# owl-analog.net
KiCad netlist of a schematic drawn in EAGLE
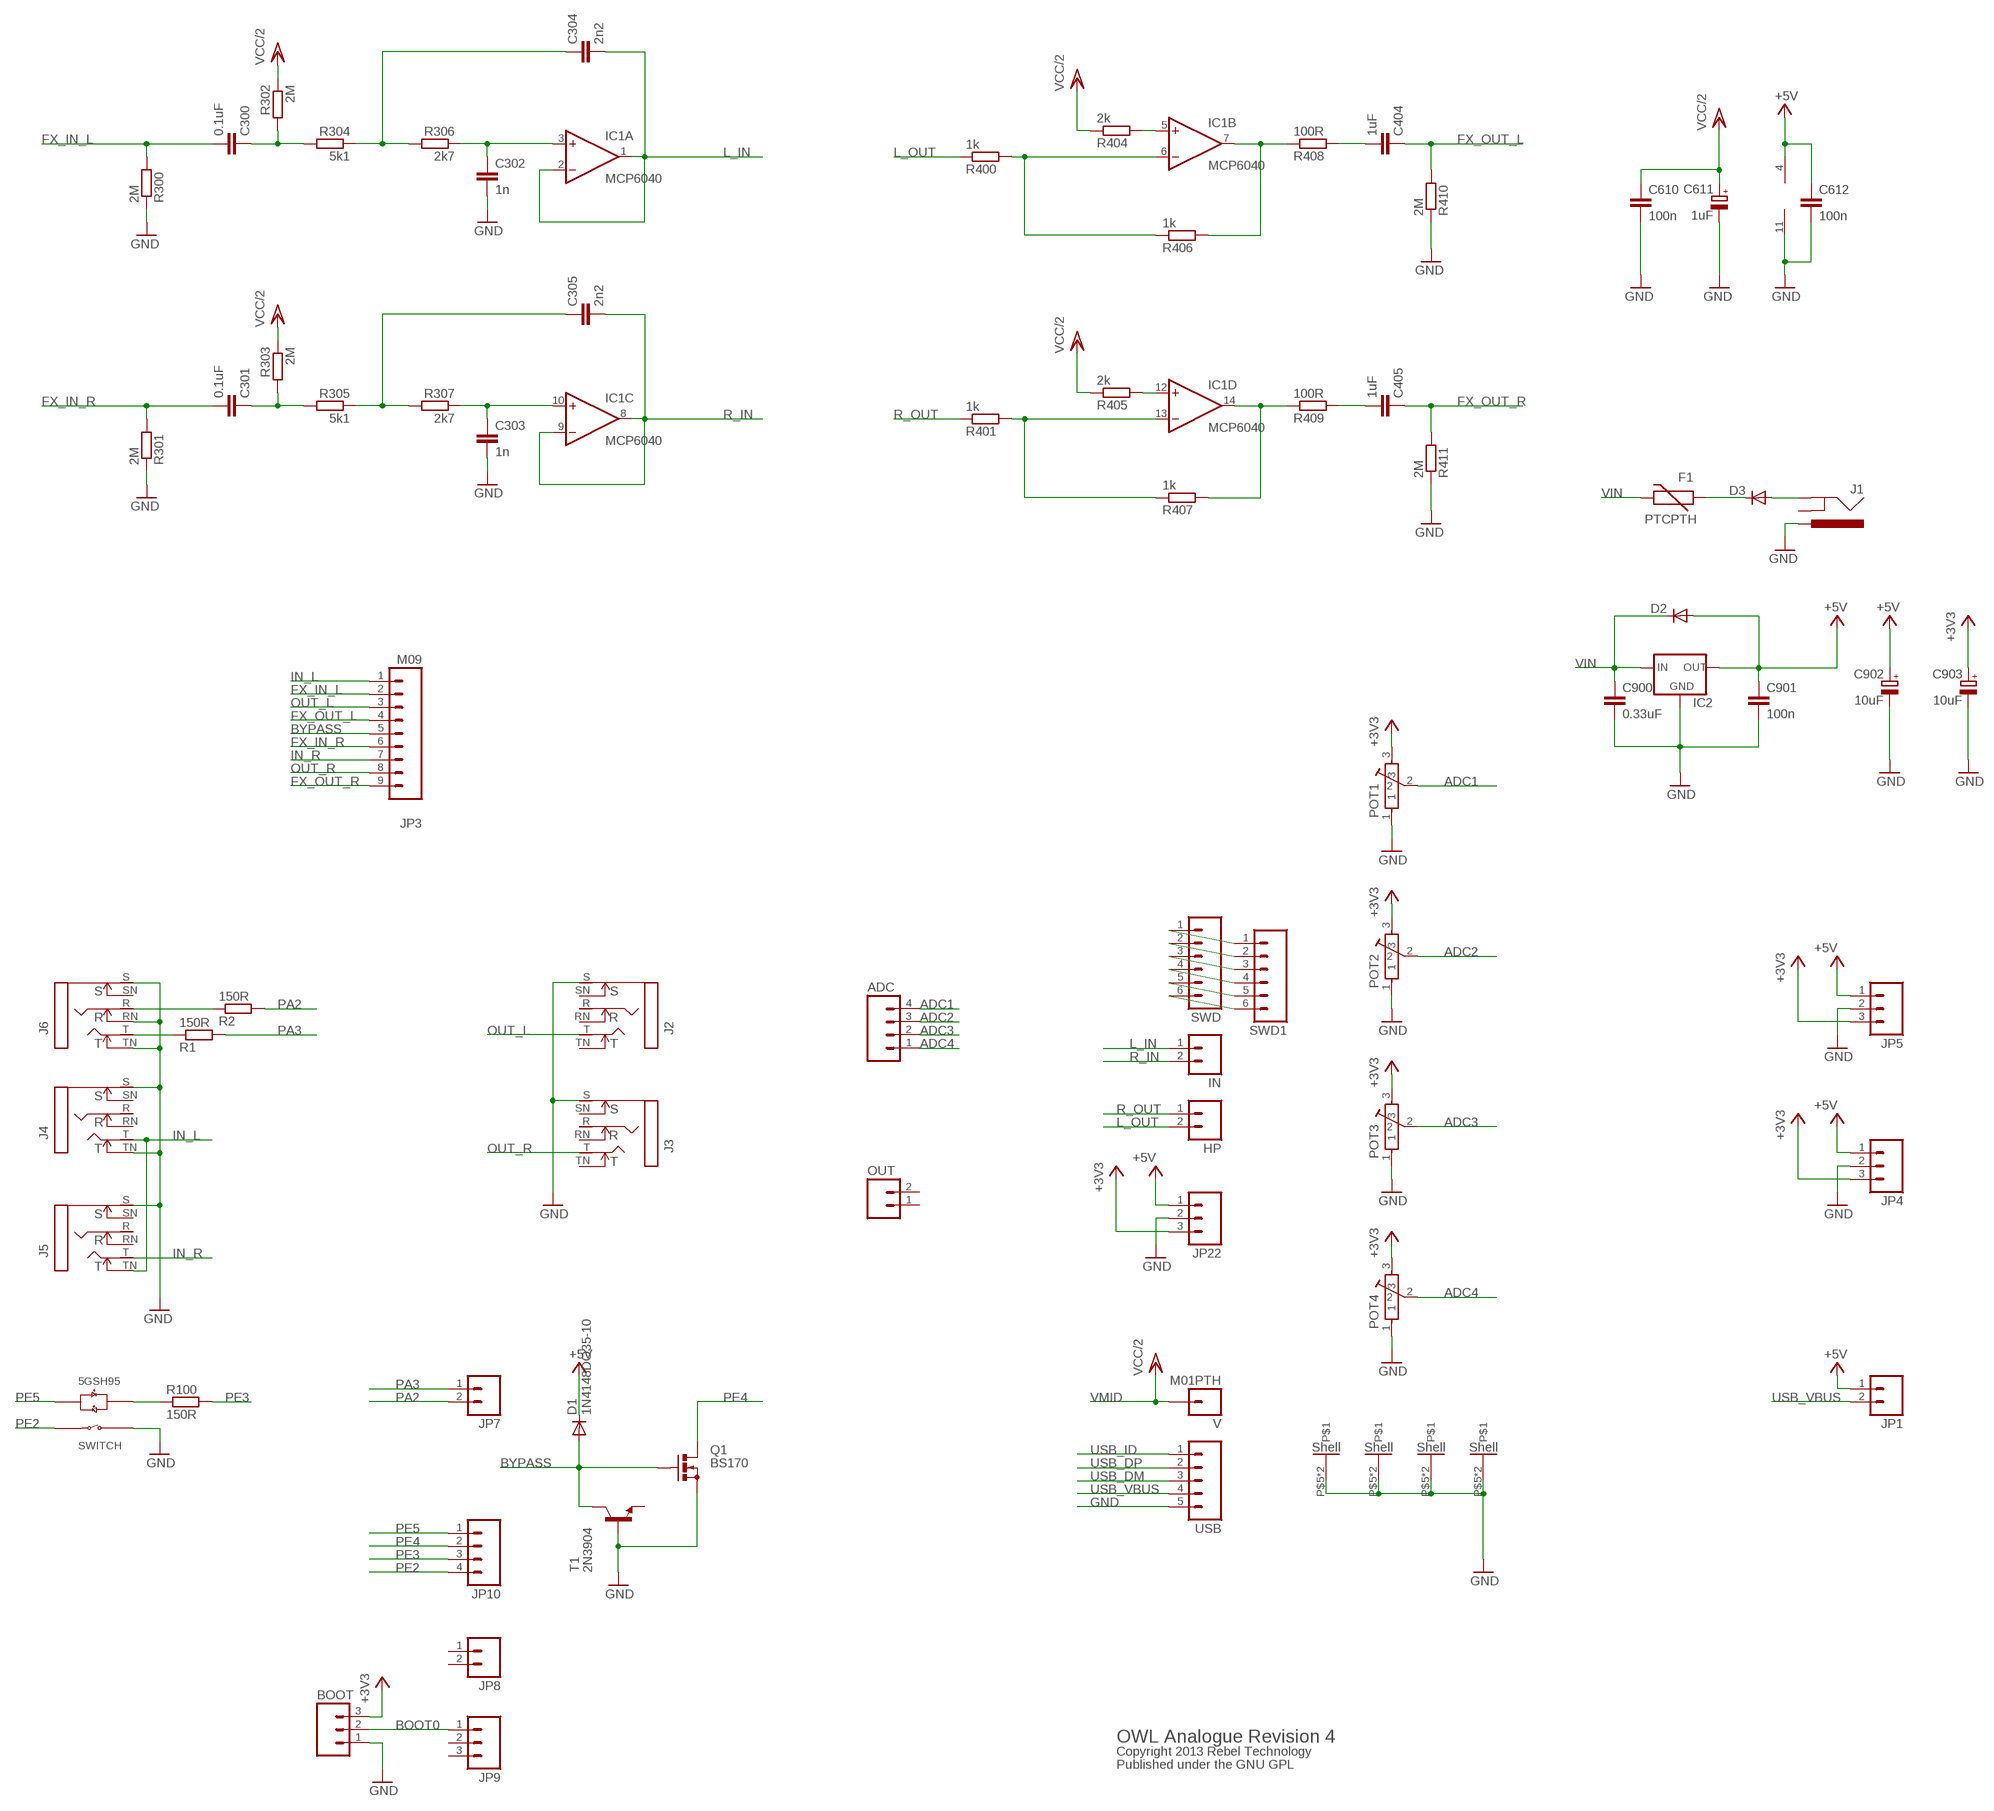
[diagram p0: schematic, sheet 1]

(export (version "E")
  (design (tool "Eeschema 10.0.6"))
  (components
    (comp (ref "ADC")
      (value "M04PTH")
      (footprint "eagle-import:1X04")
      (libsource (lib "eagle-import") (part "M04PTH"))
    )
    (comp (ref "BOOT")
      (value "M03PTH")
      (footprint "eagle-import:1X03")
      (libsource (lib "eagle-import") (part "M03PTH"))
    )
    (comp (ref "C300")
      (value "0.1uF")
      (footprint "eagle-import:C5B3.5")
      (libsource (lib "eagle-import") (part "C5/3.5"))
    )
    (comp (ref "C301")
      (value "0.1uF")
      (footprint "eagle-import:C5B3.5")
      (libsource (lib "eagle-import") (part "C5/3.5"))
    )
    (comp (ref "C302")
      (value "1n")
      (footprint "eagle-import:C5B2.5")
      (libsource (lib "eagle-import") (part "C5/2.5"))
    )
    (comp (ref "C303")
      (value "1n")
      (footprint "eagle-import:C5B2.5")
      (libsource (lib "eagle-import") (part "C5/2.5"))
    )
    (comp (ref "C304")
      (value "2n2")
      (footprint "eagle-import:C5B2.5")
      (libsource (lib "eagle-import") (part "C5/2.5"))
    )
    (comp (ref "C305")
      (value "2n2")
      (footprint "eagle-import:C050-025X075")
      (libsource (lib "eagle-import") (part "C-EU050-025X075"))
    )
    (comp (ref "C404")
      (value "1uF")
      (footprint "eagle-import:C5B5")
      (libsource (lib "eagle-import") (part "C5/5"))
    )
    (comp (ref "C405")
      (value "1uF")
      (footprint "eagle-import:C5B5")
      (libsource (lib "eagle-import") (part "C5/5"))
    )
    (comp (ref "C610")
      (value "100n")
      (footprint "eagle-import:C050-025X075")
      (libsource (lib "eagle-import") (part "C-EU050-025X075"))
    )
    (comp (ref "C611")
      (value "1uF")
      (footprint "eagle-import:E2,5-7")
      (libsource (lib "eagle-import") (part "CPOL-EUE2.5-7"))
    )
    (comp (ref "C612")
      (value "100n")
      (footprint "eagle-import:C050-025X075")
      (libsource (lib "eagle-import") (part "C-EU050-025X075"))
    )
    (comp (ref "C900")
      (value "0.33uF")
      (footprint "eagle-import:C050-025X075")
      (libsource (lib "eagle-import") (part "C-EU050-025X075"))
    )
    (comp (ref "C901")
      (value "100n")
      (footprint "eagle-import:C050-025X075")
      (libsource (lib "eagle-import") (part "C-EU050-025X075"))
    )
    (comp (ref "C902")
      (value "10uF")
      (footprint "eagle-import:E2,5-7")
      (libsource (lib "eagle-import") (part "CPOL-EUE2.5-7"))
    )
    (comp (ref "C903")
      (value "10uF")
      (footprint "eagle-import:E2,5-7")
      (libsource (lib "eagle-import") (part "CPOL-EUE2.5-7"))
    )
    (comp (ref "D1")
      (value "1N4148DO35-10")
      (footprint "eagle-import:DO35-10")
      (libsource (lib "eagle-import") (part "1N4148DO35-10"))
    )
    (comp (ref "D2")
      (value "DIODE1N4001")
      (footprint "eagle-import:DIODE-1N4001")
      (libsource (lib "eagle-import") (part "DIODE1N4001"))
    )
    (comp (ref "D3")
      (value "DIODE1N4001")
      (footprint "eagle-import:DIODE-1N4001")
      (libsource (lib "eagle-import") (part "DIODE1N4001"))
    )
    (comp (ref "F1")
      (value "PTCPTH")
      (footprint "eagle-import:PTC")
      (libsource (lib "eagle-import") (part "PTCPTH"))
    )
    (comp (ref "HP")
      (value "M02PTH")
      (footprint "eagle-import:1X02")
      (libsource (lib "eagle-import") (part "M02PTH"))
    )
    (comp (ref "IC1")
      (value "MCP6040")
      (footprint "eagle-import:DIL14")
      (libsource (lib "eagle-import") (part "TL074P"))
    )
    (comp (ref "IC2")
      (value "V_REG_78XX-TO-220")
      (footprint "eagle-import:TO-220-ALT")
      (libsource (lib "eagle-import") (part "V_REG_78XX-TO-220"))
    )
    (comp (ref "IN")
      (value "M02PTH")
      (footprint "eagle-import:1X02")
      (libsource (lib "eagle-import") (part "M02PTH"))
    )
    (comp (ref "J1")
      (value "POWER_JACKPTH")
      (footprint "eagle-import:POWER_JACK_PTH")
      (libsource (lib "eagle-import") (part "POWER_JACKPTH"))
    )
    (comp (ref "J2")
      (value "NEUTRIK_NMJ6HCD2")
      (footprint "eagle-import:NMJ6HCD2")
      (libsource (lib "eagle-import") (part "NEUTRIK_NMJ6HCD2"))
    )
    (comp (ref "J3")
      (value "NEUTRIK_NMJ6HCD2")
      (footprint "eagle-import:NMJ6HCD2")
      (libsource (lib "eagle-import") (part "NEUTRIK_NMJ6HCD2"))
    )
    (comp (ref "J4")
      (value "NEUTRIK_NMJ6HCD2")
      (footprint "eagle-import:NMJ6HCD2")
      (libsource (lib "eagle-import") (part "NEUTRIK_NMJ6HCD2"))
    )
    (comp (ref "J5")
      (value "NEUTRIK_NMJ6HCD2")
      (footprint "eagle-import:NMJ6HCD2")
      (libsource (lib "eagle-import") (part "NEUTRIK_NMJ6HCD2"))
    )
    (comp (ref "J6")
      (value "NEUTRIK_NMJ6HCD2")
      (footprint "eagle-import:NMJ6HCD2")
      (libsource (lib "eagle-import") (part "NEUTRIK_NMJ6HCD2"))
    )
    (comp (ref "JP1")
      (value "M02PTH")
      (footprint "eagle-import:1X02")
      (libsource (lib "eagle-import") (part "M02PTH"))
    )
    (comp (ref "JP3")
      (value "M09")
      (footprint "eagle-import:1X09")
      (libsource (lib "eagle-import") (part "M09"))
    )
    (comp (ref "JP4")
      (value "M03PTH")
      (footprint "eagle-import:1X03")
      (libsource (lib "eagle-import") (part "M03PTH"))
    )
    (comp (ref "JP5")
      (value "M03PTH")
      (footprint "eagle-import:1X03")
      (libsource (lib "eagle-import") (part "M03PTH"))
    )
    (comp (ref "JP7")
      (value "M02PTH")
      (footprint "eagle-import:1X02")
      (libsource (lib "eagle-import") (part "M02PTH"))
    )
    (comp (ref "JP8")
      (value "M02PTH")
      (footprint "eagle-import:1X02")
      (libsource (lib "eagle-import") (part "M02PTH"))
    )
    (comp (ref "JP9")
      (value "M03PTH")
      (footprint "eagle-import:1X03")
      (libsource (lib "eagle-import") (part "M03PTH"))
    )
    (comp (ref "JP10")
      (value "M04PTH")
      (footprint "eagle-import:1X04")
      (libsource (lib "eagle-import") (part "M04PTH"))
    )
    (comp (ref "JP22")
      (value "M03PTH")
      (footprint "eagle-import:1X03")
      (libsource (lib "eagle-import") (part "M03PTH"))
    )
    (comp (ref "OUT")
      (value "M02PTH")
      (footprint "eagle-import:1X02")
      (libsource (lib "eagle-import") (part "M02PTH"))
    )
    (comp (ref "POT1")
      (value "POT-ALPS-RK09L1140")
      (footprint "eagle-import:POT-ALPS-RK09L1140")
      (libsource (lib "eagle-import") (part "POT-ALPS-RK09L1140"))
    )
    (comp (ref "POT2")
      (value "POT-ALPS-RK09L1140")
      (footprint "eagle-import:POT-ALPS-RK09L1140")
      (libsource (lib "eagle-import") (part "POT-ALPS-RK09L1140"))
    )
    (comp (ref "POT3")
      (value "POT-ALPS-RK09L1140")
      (footprint "eagle-import:POT-ALPS-RK09L1140")
      (libsource (lib "eagle-import") (part "POT-ALPS-RK09L1140"))
    )
    (comp (ref "POT4")
      (value "POT-ALPS-RK09L1140")
      (footprint "eagle-import:POT-ALPS-RK09L1140")
      (libsource (lib "eagle-import") (part "POT-ALPS-RK09L1140"))
    )
    (comp (ref "Q1")
      (value "BS170")
      (footprint "eagle-import:SOT54E")
      (libsource (lib "eagle-import") (part "BS170"))
    )
    (comp (ref "R1")
      (value "150R")
      (footprint "eagle-import:0204_7")
      (libsource (lib "eagle-import") (part "R-EU_0204/7"))
    )
    (comp (ref "R2")
      (value "150R")
      (footprint "eagle-import:0204_7")
      (libsource (lib "eagle-import") (part "R-EU_0204/7"))
    )
    (comp (ref "R100")
      (value "150R")
      (footprint "eagle-import:0204_7")
      (libsource (lib "eagle-import") (part "R-EU_0204/7"))
    )
    (comp (ref "R300")
      (value "2M")
      (footprint "eagle-import:0204_7")
      (libsource (lib "eagle-import") (part "R-EU_0204/7"))
    )
    (comp (ref "R301")
      (value "2M")
      (footprint "eagle-import:0204_7")
      (libsource (lib "eagle-import") (part "R-EU_0204/7"))
    )
    (comp (ref "R302")
      (value "2M")
      (footprint "eagle-import:0204_7")
      (libsource (lib "eagle-import") (part "R-EU_0204/7"))
    )
    (comp (ref "R303")
      (value "2M")
      (footprint "eagle-import:0204_7")
      (libsource (lib "eagle-import") (part "R-EU_0204/7"))
    )
    (comp (ref "R304")
      (value "5k1")
      (footprint "eagle-import:0204_7")
      (libsource (lib "eagle-import") (part "R-EU_0204/7"))
    )
    (comp (ref "R305")
      (value "5k1")
      (footprint "eagle-import:0204_7")
      (libsource (lib "eagle-import") (part "R-EU_0204/7"))
    )
    (comp (ref "R306")
      (value "2k7")
      (footprint "eagle-import:0204_7")
      (libsource (lib "eagle-import") (part "R-EU_0204/7"))
    )
    (comp (ref "R307")
      (value "2k7")
      (footprint "eagle-import:0204_7")
      (libsource (lib "eagle-import") (part "R-EU_0204/7"))
    )
    (comp (ref "R400")
      (value "1k")
      (footprint "eagle-import:0204_7")
      (libsource (lib "eagle-import") (part "R-EU_0204/7"))
    )
    (comp (ref "R401")
      (value "1k")
      (footprint "eagle-import:0204_7")
      (libsource (lib "eagle-import") (part "R-EU_0204/7"))
    )
    (comp (ref "R404")
      (value "2k")
      (footprint "eagle-import:0204_7")
      (libsource (lib "eagle-import") (part "R-EU_0204/7"))
    )
    (comp (ref "R405")
      (value "2k")
      (footprint "eagle-import:0204_7")
      (libsource (lib "eagle-import") (part "R-EU_0204/7"))
    )
    (comp (ref "R406")
      (value "1k")
      (footprint "eagle-import:0204_7")
      (libsource (lib "eagle-import") (part "R-EU_0204/7"))
    )
    (comp (ref "R407")
      (value "1k")
      (footprint "eagle-import:0204_7")
      (libsource (lib "eagle-import") (part "R-EU_0204/7"))
    )
    (comp (ref "R408")
      (value "100R")
      (footprint "eagle-import:0204_7")
      (libsource (lib "eagle-import") (part "R-EU_0204/7"))
    )
    (comp (ref "R409")
      (value "100R")
      (footprint "eagle-import:0204_7")
      (libsource (lib "eagle-import") (part "R-EU_0204/7"))
    )
    (comp (ref "R410")
      (value "2M")
      (footprint "eagle-import:0204_7")
      (libsource (lib "eagle-import") (part "R-EU_0204/7"))
    )
    (comp (ref "R411")
      (value "2M")
      (footprint "eagle-import:0204_7")
      (libsource (lib "eagle-import") (part "R-EU_0204/7"))
    )
    (comp (ref "SWD")
      (value "M06SIP")
      (footprint "eagle-import:1X06")
      (libsource (lib "eagle-import") (part "M06SIP"))
    )
    (comp (ref "SWD1")
      (value "M06SIP")
      (footprint "eagle-import:1X06")
      (libsource (lib "eagle-import") (part "M06SIP"))
    )
    (comp (ref "T1")
      (value "2N3904")
      (footprint "eagle-import:TO92")
      (libsource (lib "eagle-import") (part "2N3904"))
    )
    (comp (ref "U$1")
      (value "5GTH9")
      (footprint "eagle-import:5GTH9")
      (libsource (lib "eagle-import") (part "5GTH9"))
    )
    (comp (ref "USB")
      (value "M05PTH")
      (footprint "eagle-import:1X05")
      (libsource (lib "eagle-import") (part "M05PTH"))
    )
    (comp (ref "V")
      (value "M01PTH")
      (footprint "eagle-import:1X01")
      (libsource (lib "eagle-import") (part "M01PTH"))
    )
  )
  (nets
    (net (code "1") (name "+3V3") (class "Default")
      (node (ref "BOOT") (pin "3") (pinfunction "3_3") (pintype "passive"))
      (node (ref "C903") (pin "+") (pinfunction "+_+") (pintype "passive"))
      (node (ref "JP22") (pin "3") (pinfunction "3_3") (pintype "passive"))
      (node (ref "JP4") (pin "3") (pinfunction "3_3") (pintype "passive"))
      (node (ref "JP5") (pin "3") (pinfunction "3_3") (pintype "passive"))
      (node (ref "POT1") (pin "3") (pinfunction "3_3") (pintype "bidirectional"))
      (node (ref "POT2") (pin "3") (pinfunction "3_3") (pintype "bidirectional"))
      (node (ref "POT3") (pin "3") (pinfunction "3_3") (pintype "bidirectional"))
      (node (ref "POT4") (pin "3") (pinfunction "3_3") (pintype "bidirectional"))
    )
    (net (code "2") (name "+5V") (class "Default")
      (node (ref "C612") (pin "1") (pinfunction "1_1") (pintype "passive"))
      (node (ref "C901") (pin "1") (pinfunction "1_1") (pintype "passive"))
      (node (ref "C902") (pin "+") (pinfunction "+_+") (pintype "passive"))
      (node (ref "D1") (pin "C") (pinfunction "C_C") (pintype "passive"))
      (node (ref "D2") (pin "A") (pinfunction "A_A") (pintype "passive"))
      (node (ref "IC1") (pin "4") (pinfunction "V+_4") (pintype "power_in"))
      (node (ref "IC2") (pin "OUT") (pinfunction "OUT_OUT") (pintype "output"))
      (node (ref "JP1") (pin "1") (pinfunction "1_1") (pintype "passive"))
      (node (ref "JP22") (pin "1") (pinfunction "1_1") (pintype "passive"))
      (node (ref "JP4") (pin "1") (pinfunction "1_1") (pintype "passive"))
      (node (ref "JP5") (pin "1") (pinfunction "1_1") (pintype "passive"))
    )
    (net (code "3") (name "/ADC1") (class "Default")
      (node (ref "ADC") (pin "4") (pinfunction "4_4") (pintype "passive"))
      (node (ref "POT1") (pin "2") (pinfunction "2_2") (pintype "bidirectional"))
    )
    (net (code "4") (name "/ADC2") (class "Default")
      (node (ref "ADC") (pin "3") (pinfunction "3_3") (pintype "passive"))
      (node (ref "POT2") (pin "2") (pinfunction "2_2") (pintype "bidirectional"))
    )
    (net (code "5") (name "/ADC3") (class "Default")
      (node (ref "ADC") (pin "2") (pinfunction "2_2") (pintype "passive"))
      (node (ref "POT3") (pin "2") (pinfunction "2_2") (pintype "bidirectional"))
    )
    (net (code "6") (name "/ADC4") (class "Default")
      (node (ref "ADC") (pin "1") (pinfunction "1_1") (pintype "passive"))
      (node (ref "POT4") (pin "2") (pinfunction "2_2") (pintype "bidirectional"))
    )
    (net (code "7") (name "/BOOT0") (class "Default")
      (node (ref "BOOT") (pin "2") (pinfunction "2_2") (pintype "passive"))
      (node (ref "JP9") (pin "1") (pinfunction "1_1") (pintype "passive"))
    )
    (net (code "8") (name "/BYPASS") (class "Default")
      (node (ref "D1") (pin "A") (pinfunction "A_A") (pintype "passive"))
      (node (ref "JP3") (pin "5") (pinfunction "5_5") (pintype "passive"))
      (node (ref "Q1") (pin "G") (pinfunction "G_G") (pintype "passive"))
      (node (ref "T1") (pin "1") (pinfunction "C_1") (pintype "passive"))
    )
    (net (code "9") (name "/FX_IN_L") (class "Default")
      (node (ref "C300") (pin "2") (pinfunction "2_2") (pintype "passive"))
      (node (ref "JP3") (pin "2") (pinfunction "2_2") (pintype "passive"))
      (node (ref "R300") (pin "2") (pinfunction "2_2") (pintype "passive"))
    )
    (net (code "10") (name "/FX_IN_R") (class "Default")
      (node (ref "C301") (pin "2") (pinfunction "2_2") (pintype "passive"))
      (node (ref "JP3") (pin "6") (pinfunction "6_6") (pintype "passive"))
      (node (ref "R301") (pin "2") (pinfunction "2_2") (pintype "passive"))
    )
    (net (code "11") (name "/FX_OUT_L") (class "Default")
      (node (ref "C404") (pin "1") (pinfunction "1_1") (pintype "passive"))
      (node (ref "JP3") (pin "4") (pinfunction "4_4") (pintype "passive"))
      (node (ref "R410") (pin "2") (pinfunction "2_2") (pintype "passive"))
    )
    (net (code "12") (name "/FX_OUT_R") (class "Default")
      (node (ref "C405") (pin "1") (pinfunction "1_1") (pintype "passive"))
      (node (ref "JP3") (pin "9") (pinfunction "9_9") (pintype "passive"))
      (node (ref "R411") (pin "2") (pinfunction "2_2") (pintype "passive"))
    )
    (net (code "13") (name "/IN_L") (class "Default")
      (node (ref "J4") (pin "T") (pinfunction "T_T") (pintype "passive"))
      (node (ref "J5") (pin "TN") (pinfunction "TN_TN") (pintype "passive"))
      (node (ref "JP3") (pin "1") (pinfunction "1_1") (pintype "passive"))
    )
    (net (code "14") (name "/IN_R") (class "Default")
      (node (ref "J5") (pin "T") (pinfunction "T_T") (pintype "passive"))
      (node (ref "JP3") (pin "7") (pinfunction "7_7") (pintype "passive"))
    )
    (net (code "15") (name "/L_IN") (class "Default")
      (node (ref "C304") (pin "2") (pinfunction "2_2") (pintype "passive"))
      (node (ref "IC1") (pin "1") (pinfunction "OUT_1") (pintype "output"))
      (node (ref "IC1") (pin "2") (pinfunction "-IN_2") (pintype "input"))
      (node (ref "IN") (pin "1") (pinfunction "1_1") (pintype "passive"))
    )
    (net (code "16") (name "/L_OUT") (class "Default")
      (node (ref "HP") (pin "2") (pinfunction "2_2") (pintype "passive"))
      (node (ref "R400") (pin "1") (pinfunction "1_1") (pintype "passive"))
    )
    (net (code "17") (name "/OUT_L") (class "Default")
      (node (ref "J2") (pin "T") (pinfunction "T_T") (pintype "passive"))
      (node (ref "JP3") (pin "3") (pinfunction "3_3") (pintype "passive"))
    )
    (net (code "18") (name "/OUT_R") (class "Default")
      (node (ref "J3") (pin "T") (pinfunction "T_T") (pintype "passive"))
      (node (ref "JP3") (pin "8") (pinfunction "8_8") (pintype "passive"))
    )
    (net (code "19") (name "/PA2") (class "Default")
      (node (ref "JP7") (pin "2") (pinfunction "2_2") (pintype "passive"))
      (node (ref "R2") (pin "2") (pinfunction "2_2") (pintype "passive"))
    )
    (net (code "20") (name "/PA3") (class "Default")
      (node (ref "JP7") (pin "1") (pinfunction "1_1") (pintype "passive"))
      (node (ref "R1") (pin "2") (pinfunction "2_2") (pintype "passive"))
    )
    (net (code "21") (name "/PE2") (class "Default")
      (node (ref "JP10") (pin "4") (pinfunction "4_4") (pintype "passive"))
      (node (ref "U$1") (pin "4") (pinfunction "SWITCH_A_4") (pintype "power_in"))
    )
    (net (code "22") (name "/PE3") (class "Default")
      (node (ref "JP10") (pin "3") (pinfunction "3_3") (pintype "passive"))
      (node (ref "R100") (pin "2") (pinfunction "2_2") (pintype "passive"))
    )
    (net (code "23") (name "/PE4") (class "Default")
      (node (ref "JP10") (pin "2") (pinfunction "2_2") (pintype "passive"))
      (node (ref "Q1") (pin "D") (pinfunction "D_D") (pintype "passive"))
    )
    (net (code "24") (name "/PE5") (class "Default")
      (node (ref "JP10") (pin "1") (pinfunction "1_1") (pintype "passive"))
      (node (ref "U$1") (pin "-2") (pinfunction "LED_G+_-2") (pintype "input"))
    )
    (net (code "25") (name "/R_IN") (class "Default")
      (node (ref "C305") (pin "2") (pinfunction "2_2") (pintype "passive"))
      (node (ref "IC1") (pin "8") (pinfunction "OUT_8") (pintype "output"))
      (node (ref "IC1") (pin "9") (pinfunction "-IN_9") (pintype "input"))
      (node (ref "IN") (pin "2") (pinfunction "2_2") (pintype "passive"))
    )
    (net (code "26") (name "/R_OUT") (class "Default")
      (node (ref "HP") (pin "1") (pinfunction "1_1") (pintype "passive"))
      (node (ref "R401") (pin "1") (pinfunction "1_1") (pintype "passive"))
    )
    (net (code "27") (name "/USB_DM") (class "Default")
      (node (ref "USB") (pin "3") (pinfunction "3_3") (pintype "passive"))
    )
    (net (code "28") (name "/USB_DP") (class "Default")
      (node (ref "USB") (pin "2") (pinfunction "2_2") (pintype "passive"))
    )
    (net (code "29") (name "/USB_ID") (class "Default")
      (node (ref "USB") (pin "1") (pinfunction "1_1") (pintype "passive"))
    )
    (net (code "30") (name "/USB_VBUS") (class "Default")
      (node (ref "JP1") (pin "2") (pinfunction "2_2") (pintype "passive"))
      (node (ref "USB") (pin "4") (pinfunction "4_4") (pintype "passive"))
    )
    (net (code "31") (name "/VIN") (class "Default")
      (node (ref "C900") (pin "1") (pinfunction "1_1") (pintype "passive"))
      (node (ref "D2") (pin "C") (pinfunction "C_C") (pintype "passive"))
      (node (ref "F1") (pin "P$2") (pinfunction "2_P$2") (pintype "bidirectional"))
      (node (ref "IC2") (pin "IN") (pinfunction "IN_IN") (pintype "input"))
    )
    (net (code "32") (name "GND") (class "Default")
      (node (ref "BOOT") (pin "1") (pinfunction "1_1") (pintype "passive"))
      (node (ref "C302") (pin "2") (pinfunction "2_2") (pintype "passive"))
      (node (ref "C303") (pin "2") (pinfunction "2_2") (pintype "passive"))
      (node (ref "C610") (pin "2") (pinfunction "2_2") (pintype "passive"))
      (node (ref "C611") (pin "-") (pinfunction "-_-") (pintype "passive"))
      (node (ref "C612") (pin "2") (pinfunction "2_2") (pintype "passive"))
      (node (ref "C900") (pin "2") (pinfunction "2_2") (pintype "passive"))
      (node (ref "C901") (pin "2") (pinfunction "2_2") (pintype "passive"))
      (node (ref "C902") (pin "-") (pinfunction "-_-") (pintype "passive"))
      (node (ref "C903") (pin "-") (pinfunction "-_-") (pintype "passive"))
      (node (ref "IC1") (pin "11") (pinfunction "V-_11") (pintype "power_in"))
      (node (ref "IC2") (pin "GND") (pinfunction "GND_GND") (pintype "input"))
      (node (ref "J1") (pin "PWR") (pinfunction "PWR_PWR") (pintype "bidirectional"))
      (node (ref "J2") (pin "S") (pinfunction "S_S") (pintype "passive"))
      (node (ref "J3") (pin "S") (pinfunction "S_S") (pintype "passive"))
      (node (ref "J4") (pin "S") (pinfunction "S_S") (pintype "passive"))
      (node (ref "J4") (pin "TN") (pinfunction "TN_TN") (pintype "passive"))
      (node (ref "J5") (pin "S") (pinfunction "S_S") (pintype "passive"))
      (node (ref "J6") (pin "RN") (pinfunction "RN_RN") (pintype "passive"))
      (node (ref "J6") (pin "S") (pinfunction "S_S") (pintype "passive"))
      (node (ref "J6") (pin "TN") (pinfunction "TN_TN") (pintype "passive"))
      (node (ref "JP22") (pin "2") (pinfunction "2_2") (pintype "passive"))
      (node (ref "JP4") (pin "2") (pinfunction "2_2") (pintype "passive"))
      (node (ref "JP5") (pin "2") (pinfunction "2_2") (pintype "passive"))
      (node (ref "POT1") (pin "1") (pinfunction "1_1") (pintype "bidirectional"))
      (node (ref "POT1") (pin "P$5") (pinfunction "P$1_P$5") (pintype "bidirectional"))
      (node (ref "POT1") (pin "P$6") (pinfunction "P$1_P$6") (pintype "bidirectional"))
      (node (ref "POT2") (pin "1") (pinfunction "1_1") (pintype "bidirectional"))
      (node (ref "POT2") (pin "P$5") (pinfunction "P$1_P$5") (pintype "bidirectional"))
      (node (ref "POT2") (pin "P$6") (pinfunction "P$1_P$6") (pintype "bidirectional"))
      (node (ref "POT3") (pin "1") (pinfunction "1_1") (pintype "bidirectional"))
      (node (ref "POT3") (pin "P$5") (pinfunction "P$1_P$5") (pintype "bidirectional"))
      (node (ref "POT3") (pin "P$6") (pinfunction "P$1_P$6") (pintype "bidirectional"))
      (node (ref "POT4") (pin "1") (pinfunction "1_1") (pintype "bidirectional"))
      (node (ref "POT4") (pin "P$5") (pinfunction "P$1_P$5") (pintype "bidirectional"))
      (node (ref "POT4") (pin "P$6") (pinfunction "P$1_P$6") (pintype "bidirectional"))
      (node (ref "Q1") (pin "S") (pinfunction "S_S") (pintype "passive"))
      (node (ref "R300") (pin "1") (pinfunction "1_1") (pintype "passive"))
      (node (ref "R301") (pin "1") (pinfunction "1_1") (pintype "passive"))
      (node (ref "R410") (pin "1") (pinfunction "1_1") (pintype "passive"))
      (node (ref "R411") (pin "1") (pinfunction "1_1") (pintype "passive"))
      (node (ref "T1") (pin "2") (pinfunction "B_2") (pintype "passive"))
      (node (ref "U$1") (pin "1") (pinfunction "SWITCH_B_1") (pintype "power_in"))
      (node (ref "USB") (pin "5") (pinfunction "5_5") (pintype "passive"))
    )
    (net (code "33") (name "Net-(C300-Pad1)") (class "Default")
      (node (ref "C300") (pin "1") (pinfunction "1_1") (pintype "passive"))
      (node (ref "R302") (pin "2") (pinfunction "2_2") (pintype "passive"))
      (node (ref "R304") (pin "2") (pinfunction "2_2") (pintype "passive"))
    )
    (net (code "34") (name "Net-(C301-Pad1)") (class "Default")
      (node (ref "C301") (pin "1") (pinfunction "1_1") (pintype "passive"))
      (node (ref "R303") (pin "2") (pinfunction "2_2") (pintype "passive"))
      (node (ref "R305") (pin "2") (pinfunction "2_2") (pintype "passive"))
    )
    (net (code "35") (name "Net-(C304-Pad1)") (class "Default")
      (node (ref "C304") (pin "1") (pinfunction "1_1") (pintype "passive"))
      (node (ref "R304") (pin "1") (pinfunction "1_1") (pintype "passive"))
      (node (ref "R306") (pin "2") (pinfunction "2_2") (pintype "passive"))
    )
    (net (code "36") (name "Net-(C305-Pad1)") (class "Default")
      (node (ref "C305") (pin "1") (pinfunction "1_1") (pintype "passive"))
      (node (ref "R305") (pin "1") (pinfunction "1_1") (pintype "passive"))
      (node (ref "R307") (pin "2") (pinfunction "2_2") (pintype "passive"))
    )
    (net (code "37") (name "Net-(C404-Pad2)") (class "Default")
      (node (ref "C404") (pin "2") (pinfunction "2_2") (pintype "passive"))
      (node (ref "R408") (pin "2") (pinfunction "2_2") (pintype "passive"))
    )
    (net (code "38") (name "Net-(C405-Pad2)") (class "Default")
      (node (ref "C405") (pin "2") (pinfunction "2_2") (pintype "passive"))
      (node (ref "R409") (pin "2") (pinfunction "2_2") (pintype "passive"))
    )
    (net (code "39") (name "Net-(D3-PadA)") (class "Default")
      (node (ref "D3") (pin "A") (pinfunction "A_A") (pintype "passive"))
      (node (ref "J1") (pin "GND") (pinfunction "GND_GND") (pintype "bidirectional"))
    )
    (net (code "40") (name "Net-(F1-1)") (class "Default")
      (node (ref "D3") (pin "C") (pinfunction "C_C") (pintype "passive"))
      (node (ref "F1") (pin "P$1") (pinfunction "1_P$1") (pintype "bidirectional"))
    )
    (net (code "41") (name "Net-(IC1A-+IN)") (class "Default")
      (node (ref "C302") (pin "1") (pinfunction "1_1") (pintype "passive"))
      (node (ref "IC1") (pin "3") (pinfunction "+IN_3") (pintype "input"))
      (node (ref "R306") (pin "1") (pinfunction "1_1") (pintype "passive"))
    )
    (net (code "42") (name "Net-(IC1B-+IN)") (class "Default")
      (node (ref "IC1") (pin "5") (pinfunction "+IN_5") (pintype "input"))
      (node (ref "R404") (pin "2") (pinfunction "2_2") (pintype "passive"))
    )
    (net (code "43") (name "Net-(IC1B--IN)") (class "Default")
      (node (ref "IC1") (pin "6") (pinfunction "-IN_6") (pintype "input"))
      (node (ref "R400") (pin "2") (pinfunction "2_2") (pintype "passive"))
      (node (ref "R406") (pin "1") (pinfunction "1_1") (pintype "passive"))
    )
    (net (code "44") (name "Net-(IC1B-OUT)") (class "Default")
      (node (ref "IC1") (pin "7") (pinfunction "OUT_7") (pintype "output"))
      (node (ref "R406") (pin "2") (pinfunction "2_2") (pintype "passive"))
      (node (ref "R408") (pin "1") (pinfunction "1_1") (pintype "passive"))
    )
    (net (code "45") (name "Net-(IC1C-+IN)") (class "Default")
      (node (ref "C303") (pin "1") (pinfunction "1_1") (pintype "passive"))
      (node (ref "IC1") (pin "10") (pinfunction "+IN_10") (pintype "input"))
      (node (ref "R307") (pin "1") (pinfunction "1_1") (pintype "passive"))
    )
    (net (code "46") (name "Net-(IC1D-+IN)") (class "Default")
      (node (ref "IC1") (pin "12") (pinfunction "+IN_12") (pintype "input"))
      (node (ref "R405") (pin "2") (pinfunction "2_2") (pintype "passive"))
    )
    (net (code "47") (name "Net-(IC1D--IN)") (class "Default")
      (node (ref "IC1") (pin "13") (pinfunction "-IN_13") (pintype "input"))
      (node (ref "R401") (pin "2") (pinfunction "2_2") (pintype "passive"))
      (node (ref "R407") (pin "1") (pinfunction "1_1") (pintype "passive"))
    )
    (net (code "48") (name "Net-(IC1D-OUT)") (class "Default")
      (node (ref "IC1") (pin "14") (pinfunction "OUT_14") (pintype "output"))
      (node (ref "R407") (pin "2") (pinfunction "2_2") (pintype "passive"))
      (node (ref "R409") (pin "1") (pinfunction "1_1") (pintype "passive"))
    )
    (net (code "49") (name "Net-(J6-PadR)") (class "Default")
      (node (ref "J6") (pin "R") (pinfunction "R_R") (pintype "passive"))
      (node (ref "R2") (pin "1") (pinfunction "1_1") (pintype "passive"))
    )
    (net (code "50") (name "Net-(J6-PadT)") (class "Default")
      (node (ref "J6") (pin "T") (pinfunction "T_T") (pintype "passive"))
      (node (ref "R1") (pin "1") (pinfunction "1_1") (pintype "passive"))
    )
    (net (code "51") (name "Net-(SWD-Pad1)") (class "Default")
      (node (ref "SWD") (pin "1") (pinfunction "1_1") (pintype "passive"))
      (node (ref "SWD1") (pin "1") (pinfunction "1_1") (pintype "passive"))
    )
    (net (code "52") (name "Net-(SWD-Pad2)") (class "Default")
      (node (ref "SWD") (pin "2") (pinfunction "2_2") (pintype "passive"))
      (node (ref "SWD1") (pin "2") (pinfunction "2_2") (pintype "passive"))
    )
    (net (code "53") (name "Net-(SWD-Pad3)") (class "Default")
      (node (ref "SWD") (pin "3") (pinfunction "3_3") (pintype "passive"))
      (node (ref "SWD1") (pin "3") (pinfunction "3_3") (pintype "passive"))
    )
    (net (code "54") (name "Net-(SWD-Pad4)") (class "Default")
      (node (ref "SWD") (pin "4") (pinfunction "4_4") (pintype "passive"))
      (node (ref "SWD1") (pin "4") (pinfunction "4_4") (pintype "passive"))
    )
    (net (code "55") (name "Net-(SWD-Pad5)") (class "Default")
      (node (ref "SWD") (pin "5") (pinfunction "5_5") (pintype "passive"))
      (node (ref "SWD1") (pin "5") (pinfunction "5_5") (pintype "passive"))
    )
    (net (code "56") (name "Net-(SWD-Pad6)") (class "Default")
      (node (ref "SWD") (pin "6") (pinfunction "6_6") (pintype "passive"))
      (node (ref "SWD1") (pin "6") (pinfunction "6_6") (pintype "passive"))
    )
    (net (code "57") (name "Net-(U$1-LED_R+)") (class "Default")
      (node (ref "R100") (pin "1") (pinfunction "1_1") (pintype "passive"))
      (node (ref "U$1") (pin "+3") (pinfunction "LED_R+_+3") (pintype "input"))
    )
    (net (code "58") (name "VCC{slash}2") (class "Default")
      (node (ref "C610") (pin "1") (pinfunction "1_1") (pintype "passive"))
      (node (ref "C611") (pin "+") (pinfunction "+_+") (pintype "passive"))
      (node (ref "R302") (pin "1") (pinfunction "1_1") (pintype "passive"))
      (node (ref "R303") (pin "1") (pinfunction "1_1") (pintype "passive"))
      (node (ref "R404") (pin "1") (pinfunction "1_1") (pintype "passive"))
      (node (ref "R405") (pin "1") (pinfunction "1_1") (pintype "passive"))
      (node (ref "V") (pin "1") (pinfunction "1_1") (pintype "passive"))
    )
    (net (code "59") (name "unconnected-(J1-PadGNDBREAK)") (class "Default")
      (node (ref "J1") (pin "GNDBREAK") (pinfunction "GNDBREAK_GNDBREAK") (pintype "bidirectional"))
    )
    (net (code "60") (name "unconnected-(J2-PadR)") (class "Default")
      (node (ref "J2") (pin "R") (pinfunction "R_R") (pintype "passive"))
    )
    (net (code "61") (name "unconnected-(J2-PadRN)") (class "Default")
      (node (ref "J2") (pin "RN") (pinfunction "RN_RN") (pintype "passive"))
    )
    (net (code "62") (name "unconnected-(J2-PadSN)") (class "Default")
      (node (ref "J2") (pin "SN") (pinfunction "SN_SN") (pintype "passive"))
    )
    (net (code "63") (name "unconnected-(J2-PadTN)") (class "Default")
      (node (ref "J2") (pin "TN") (pinfunction "TN_TN") (pintype "passive"))
    )
    (net (code "64") (name "unconnected-(J3-PadR)") (class "Default")
      (node (ref "J3") (pin "R") (pinfunction "R_R") (pintype "passive"))
    )
    (net (code "65") (name "unconnected-(J3-PadRN)") (class "Default")
      (node (ref "J3") (pin "RN") (pinfunction "RN_RN") (pintype "passive"))
    )
    (net (code "66") (name "unconnected-(J3-PadSN)") (class "Default")
      (node (ref "J3") (pin "SN") (pinfunction "SN_SN") (pintype "passive"))
    )
    (net (code "67") (name "unconnected-(J3-PadTN)") (class "Default")
      (node (ref "J3") (pin "TN") (pinfunction "TN_TN") (pintype "passive"))
    )
    (net (code "68") (name "unconnected-(J4-PadR)") (class "Default")
      (node (ref "J4") (pin "R") (pinfunction "R_R") (pintype "passive"))
    )
    (net (code "69") (name "unconnected-(J4-PadRN)") (class "Default")
      (node (ref "J4") (pin "RN") (pinfunction "RN_RN") (pintype "passive"))
    )
    (net (code "70") (name "unconnected-(J4-PadSN)") (class "Default")
      (node (ref "J4") (pin "SN") (pinfunction "SN_SN") (pintype "passive"))
    )
    (net (code "71") (name "unconnected-(J5-PadR)") (class "Default")
      (node (ref "J5") (pin "R") (pinfunction "R_R") (pintype "passive"))
    )
    (net (code "72") (name "unconnected-(J5-PadRN)") (class "Default")
      (node (ref "J5") (pin "RN") (pinfunction "RN_RN") (pintype "passive"))
    )
    (net (code "73") (name "unconnected-(J5-PadSN)") (class "Default")
      (node (ref "J5") (pin "SN") (pinfunction "SN_SN") (pintype "passive"))
    )
    (net (code "74") (name "unconnected-(J6-PadSN)") (class "Default")
      (node (ref "J6") (pin "SN") (pinfunction "SN_SN") (pintype "passive"))
    )
    (net (code "75") (name "unconnected-(JP8-Pad1)") (class "Default")
      (node (ref "JP8") (pin "1") (pinfunction "1_1") (pintype "passive"))
    )
    (net (code "76") (name "unconnected-(JP8-Pad2)") (class "Default")
      (node (ref "JP8") (pin "2") (pinfunction "2_2") (pintype "passive"))
    )
    (net (code "77") (name "unconnected-(JP9-Pad2)") (class "Default")
      (node (ref "JP9") (pin "2") (pinfunction "2_2") (pintype "passive"))
    )
    (net (code "78") (name "unconnected-(JP9-Pad3)") (class "Default")
      (node (ref "JP9") (pin "3") (pinfunction "3_3") (pintype "passive"))
    )
    (net (code "79") (name "unconnected-(OUT-Pad1)") (class "Default")
      (node (ref "OUT") (pin "1") (pinfunction "1_1") (pintype "passive"))
    )
    (net (code "80") (name "unconnected-(OUT-Pad2)") (class "Default")
      (node (ref "OUT") (pin "2") (pinfunction "2_2") (pintype "passive"))
    )
    (net (code "81") (name "unconnected-(T1-E-Pad3)") (class "Default")
      (node (ref "T1") (pin "3") (pinfunction "E_3") (pintype "passive"))
    )
  )
)
